# teensyShield1_5.net
KiCad netlist of a schematic drawn in EAGLE
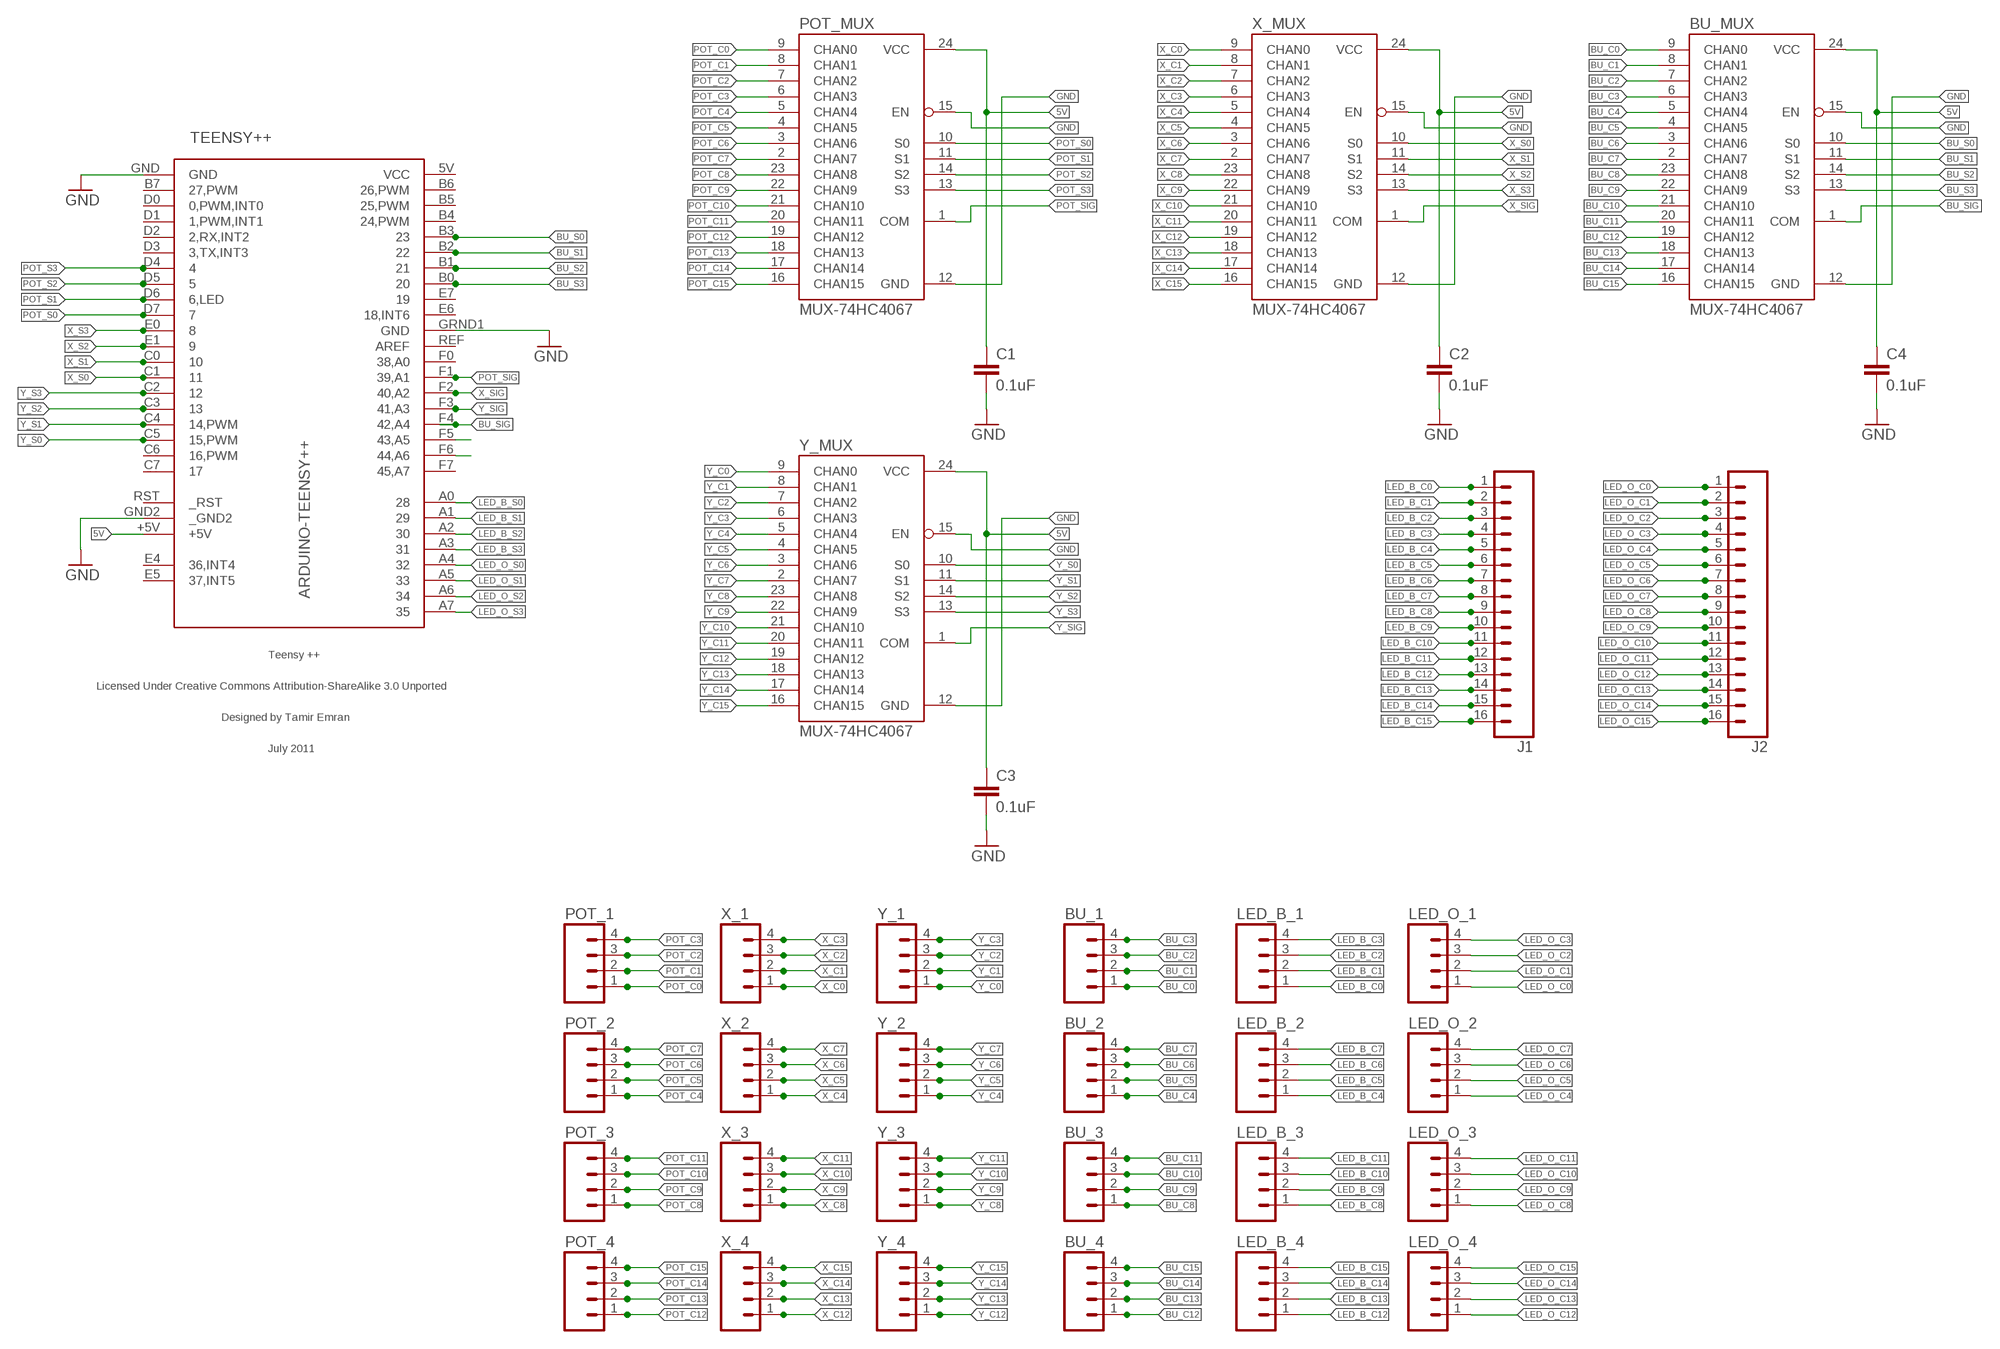
[diagram p0: schematic, sheet 1]

(export (version "E")
  (design (tool "Eeschema 10.0.6"))
  (components
    (comp (ref "BU_1")
      (value "M04NO_SILK_ALL_ROUND")
      (footprint "eagle-import:1X04_NO_SILK_ALL_ROUND")
      (libsource (lib "eagle-import") (part "M04NO_SILK_ALL_ROUND"))
    )
    (comp (ref "BU_2")
      (value "M04NO_SILK_ALL_ROUND")
      (footprint "eagle-import:1X04_NO_SILK_ALL_ROUND")
      (libsource (lib "eagle-import") (part "M04NO_SILK_ALL_ROUND"))
    )
    (comp (ref "BU_3")
      (value "M04NO_SILK_ALL_ROUND")
      (footprint "eagle-import:1X04_NO_SILK_ALL_ROUND")
      (libsource (lib "eagle-import") (part "M04NO_SILK_ALL_ROUND"))
    )
    (comp (ref "BU_4")
      (value "M04NO_SILK_ALL_ROUND")
      (footprint "eagle-import:1X04_NO_SILK_ALL_ROUND")
      (libsource (lib "eagle-import") (part "M04NO_SILK_ALL_ROUND"))
    )
    (comp (ref "BU_MUX")
      (value "MUX-74HC4067")
      (footprint "eagle-import:SSOP24")
      (libsource (lib "eagle-import") (part "MUX-74HC4067SMD"))
    )
    (comp (ref "C1")
      (value "0.1uF")
      (footprint "eagle-import:0603")
      (libsource (lib "eagle-import") (part "CAP0603"))
    )
    (comp (ref "C2")
      (value "0.1uF")
      (footprint "eagle-import:0603")
      (libsource (lib "eagle-import") (part "CAP0603"))
    )
    (comp (ref "C3")
      (value "0.1uF")
      (footprint "eagle-import:0603")
      (libsource (lib "eagle-import") (part "CAP0603"))
    )
    (comp (ref "C4")
      (value "0.1uF")
      (footprint "eagle-import:0603")
      (libsource (lib "eagle-import") (part "CAP0603"))
    )
    (comp (ref "J1")
      (value "M16MACHIINE-PIN_LOCK")
      (footprint "eagle-import:1X16_MACHINE-PIN-HEADER_LOCK.004")
      (libsource (lib "eagle-import") (part "M16MACHIINE-PIN_LOCK"))
    )
    (comp (ref "J2")
      (value "M16MACHIINE-PIN_LOCK")
      (footprint "eagle-import:1X16_MACHINE-PIN-HEADER_LOCK.004")
      (libsource (lib "eagle-import") (part "M16MACHIINE-PIN_LOCK"))
    )
    (comp (ref "LED_B_1")
      (value "M04NO_SILK_ALL_ROUND")
      (footprint "eagle-import:1X04_NO_SILK_ALL_ROUND")
      (libsource (lib "eagle-import") (part "M04NO_SILK_ALL_ROUND"))
    )
    (comp (ref "LED_B_2")
      (value "M04NO_SILK_ALL_ROUND")
      (footprint "eagle-import:1X04_NO_SILK_ALL_ROUND")
      (libsource (lib "eagle-import") (part "M04NO_SILK_ALL_ROUND"))
    )
    (comp (ref "LED_B_3")
      (value "M04NO_SILK_ALL_ROUND")
      (footprint "eagle-import:1X04_NO_SILK_ALL_ROUND")
      (libsource (lib "eagle-import") (part "M04NO_SILK_ALL_ROUND"))
    )
    (comp (ref "LED_B_4")
      (value "M04NO_SILK_ALL_ROUND")
      (footprint "eagle-import:1X04_NO_SILK_ALL_ROUND")
      (libsource (lib "eagle-import") (part "M04NO_SILK_ALL_ROUND"))
    )
    (comp (ref "LED_O_1")
      (value "M04NO_SILK_ALL_ROUND")
      (footprint "eagle-import:1X04_NO_SILK_ALL_ROUND")
      (libsource (lib "eagle-import") (part "M04NO_SILK_ALL_ROUND"))
    )
    (comp (ref "LED_O_2")
      (value "M04NO_SILK_ALL_ROUND")
      (footprint "eagle-import:1X04_NO_SILK_ALL_ROUND")
      (libsource (lib "eagle-import") (part "M04NO_SILK_ALL_ROUND"))
    )
    (comp (ref "LED_O_3")
      (value "M04NO_SILK_ALL_ROUND")
      (footprint "eagle-import:1X04_NO_SILK_ALL_ROUND")
      (libsource (lib "eagle-import") (part "M04NO_SILK_ALL_ROUND"))
    )
    (comp (ref "LED_O_4")
      (value "M04NO_SILK_ALL_ROUND")
      (footprint "eagle-import:1X04_NO_SILK_ALL_ROUND")
      (libsource (lib "eagle-import") (part "M04NO_SILK_ALL_ROUND"))
    )
    (comp (ref "POT_1")
      (value "M04NO_SILK_ALL_ROUND")
      (footprint "eagle-import:1X04_NO_SILK_ALL_ROUND")
      (libsource (lib "eagle-import") (part "M04NO_SILK_ALL_ROUND"))
    )
    (comp (ref "POT_2")
      (value "M04NO_SILK_ALL_ROUND")
      (footprint "eagle-import:1X04_NO_SILK_ALL_ROUND")
      (libsource (lib "eagle-import") (part "M04NO_SILK_ALL_ROUND"))
    )
    (comp (ref "POT_3")
      (value "M04NO_SILK_ALL_ROUND")
      (footprint "eagle-import:1X04_NO_SILK_ALL_ROUND")
      (libsource (lib "eagle-import") (part "M04NO_SILK_ALL_ROUND"))
    )
    (comp (ref "POT_4")
      (value "M04NO_SILK_ALL_ROUND")
      (footprint "eagle-import:1X04_NO_SILK_ALL_ROUND")
      (libsource (lib "eagle-import") (part "M04NO_SILK_ALL_ROUND"))
    )
    (comp (ref "POT_MUX")
      (value "MUX-74HC4067")
      (footprint "eagle-import:SSOP24")
      (libsource (lib "eagle-import") (part "MUX-74HC4067SMD"))
    )
    (comp (ref "TEENSY++")
      (value "ARDUINO-TEENSY++")
      (footprint "eagle-import:TEENSY++")
      (libsource (lib "eagle-import") (part "ARDUINO-TEENSY++"))
    )
    (comp (ref "X_1")
      (value "M04NO_SILK_ALL_ROUND")
      (footprint "eagle-import:1X04_NO_SILK_ALL_ROUND")
      (libsource (lib "eagle-import") (part "M04NO_SILK_ALL_ROUND"))
    )
    (comp (ref "X_2")
      (value "M04NO_SILK_ALL_ROUND")
      (footprint "eagle-import:1X04_NO_SILK_ALL_ROUND")
      (libsource (lib "eagle-import") (part "M04NO_SILK_ALL_ROUND"))
    )
    (comp (ref "X_3")
      (value "M04NO_SILK_ALL_ROUND")
      (footprint "eagle-import:1X04_NO_SILK_ALL_ROUND")
      (libsource (lib "eagle-import") (part "M04NO_SILK_ALL_ROUND"))
    )
    (comp (ref "X_4")
      (value "M04NO_SILK_ALL_ROUND")
      (footprint "eagle-import:1X04_NO_SILK_ALL_ROUND")
      (libsource (lib "eagle-import") (part "M04NO_SILK_ALL_ROUND"))
    )
    (comp (ref "X_MUX")
      (value "MUX-74HC4067")
      (footprint "eagle-import:SSOP24")
      (libsource (lib "eagle-import") (part "MUX-74HC4067SMD"))
    )
    (comp (ref "Y_1")
      (value "M04NO_SILK_ALL_ROUND")
      (footprint "eagle-import:1X04_NO_SILK_ALL_ROUND")
      (libsource (lib "eagle-import") (part "M04NO_SILK_ALL_ROUND"))
    )
    (comp (ref "Y_2")
      (value "M04NO_SILK_ALL_ROUND")
      (footprint "eagle-import:1X04_NO_SILK_ALL_ROUND")
      (libsource (lib "eagle-import") (part "M04NO_SILK_ALL_ROUND"))
    )
    (comp (ref "Y_3")
      (value "M04NO_SILK_ALL_ROUND")
      (footprint "eagle-import:1X04_NO_SILK_ALL_ROUND")
      (libsource (lib "eagle-import") (part "M04NO_SILK_ALL_ROUND"))
    )
    (comp (ref "Y_4")
      (value "M04NO_SILK_ALL_ROUND")
      (footprint "eagle-import:1X04_NO_SILK_ALL_ROUND")
      (libsource (lib "eagle-import") (part "M04NO_SILK_ALL_ROUND"))
    )
    (comp (ref "Y_MUX")
      (value "MUX-74HC4067")
      (footprint "eagle-import:SSOP24")
      (libsource (lib "eagle-import") (part "MUX-74HC4067SMD"))
    )
  )
  (nets
    (net (code "1") (name "/VCC") (class "Default")
      (node (ref "TEENSY++") (pin "5V") (pinfunction "VCC_5V") (pintype "power_in"))
    )
    (net (code "2") (name "5V") (class "Default")
      (node (ref "BU_MUX") (pin "24") (pinfunction "VCC_24") (pintype "bidirectional"))
      (node (ref "C1") (pin "1") (pinfunction "1_1") (pintype "passive"))
      (node (ref "C2") (pin "1") (pinfunction "1_1") (pintype "passive"))
      (node (ref "C3") (pin "1") (pinfunction "1_1") (pintype "passive"))
      (node (ref "C4") (pin "1") (pinfunction "1_1") (pintype "passive"))
      (node (ref "POT_MUX") (pin "24") (pinfunction "VCC_24") (pintype "bidirectional"))
      (node (ref "X_MUX") (pin "24") (pinfunction "VCC_24") (pintype "bidirectional"))
      (node (ref "Y_MUX") (pin "24") (pinfunction "VCC_24") (pintype "bidirectional"))
    )
    (net (code "3") (name "BU_C0") (class "Default")
      (node (ref "BU_1") (pin "1") (pinfunction "1_1") (pintype "passive"))
      (node (ref "BU_MUX") (pin "9") (pinfunction "CHAN0_9") (pintype "bidirectional"))
    )
    (net (code "4") (name "BU_C1") (class "Default")
      (node (ref "BU_1") (pin "2") (pinfunction "2_2") (pintype "passive"))
      (node (ref "BU_MUX") (pin "8") (pinfunction "CHAN1_8") (pintype "bidirectional"))
    )
    (net (code "5") (name "BU_C2") (class "Default")
      (node (ref "BU_1") (pin "3") (pinfunction "3_3") (pintype "passive"))
      (node (ref "BU_MUX") (pin "7") (pinfunction "CHAN2_7") (pintype "bidirectional"))
    )
    (net (code "6") (name "BU_C3") (class "Default")
      (node (ref "BU_1") (pin "4") (pinfunction "4_4") (pintype "passive"))
      (node (ref "BU_MUX") (pin "6") (pinfunction "CHAN3_6") (pintype "bidirectional"))
    )
    (net (code "7") (name "BU_C4") (class "Default")
      (node (ref "BU_2") (pin "1") (pinfunction "1_1") (pintype "passive"))
      (node (ref "BU_MUX") (pin "5") (pinfunction "CHAN4_5") (pintype "bidirectional"))
    )
    (net (code "8") (name "BU_C5") (class "Default")
      (node (ref "BU_2") (pin "2") (pinfunction "2_2") (pintype "passive"))
      (node (ref "BU_MUX") (pin "4") (pinfunction "CHAN5_4") (pintype "bidirectional"))
    )
    (net (code "9") (name "BU_C6") (class "Default")
      (node (ref "BU_2") (pin "3") (pinfunction "3_3") (pintype "passive"))
      (node (ref "BU_MUX") (pin "3") (pinfunction "CHAN6_3") (pintype "bidirectional"))
    )
    (net (code "10") (name "BU_C7") (class "Default")
      (node (ref "BU_2") (pin "4") (pinfunction "4_4") (pintype "passive"))
      (node (ref "BU_MUX") (pin "2") (pinfunction "CHAN7_2") (pintype "bidirectional"))
    )
    (net (code "11") (name "BU_C8") (class "Default")
      (node (ref "BU_3") (pin "1") (pinfunction "1_1") (pintype "passive"))
      (node (ref "BU_MUX") (pin "23") (pinfunction "CHAN8_23") (pintype "bidirectional"))
    )
    (net (code "12") (name "BU_C9") (class "Default")
      (node (ref "BU_3") (pin "2") (pinfunction "2_2") (pintype "passive"))
      (node (ref "BU_MUX") (pin "22") (pinfunction "CHAN9_22") (pintype "bidirectional"))
    )
    (net (code "13") (name "BU_C10") (class "Default")
      (node (ref "BU_3") (pin "3") (pinfunction "3_3") (pintype "passive"))
      (node (ref "BU_MUX") (pin "21") (pinfunction "CHAN10_21") (pintype "bidirectional"))
    )
    (net (code "14") (name "BU_C11") (class "Default")
      (node (ref "BU_3") (pin "4") (pinfunction "4_4") (pintype "passive"))
      (node (ref "BU_MUX") (pin "20") (pinfunction "CHAN11_20") (pintype "bidirectional"))
    )
    (net (code "15") (name "BU_C12") (class "Default")
      (node (ref "BU_4") (pin "1") (pinfunction "1_1") (pintype "passive"))
      (node (ref "BU_MUX") (pin "19") (pinfunction "CHAN12_19") (pintype "bidirectional"))
    )
    (net (code "16") (name "BU_C13") (class "Default")
      (node (ref "BU_4") (pin "2") (pinfunction "2_2") (pintype "passive"))
      (node (ref "BU_MUX") (pin "18") (pinfunction "CHAN13_18") (pintype "bidirectional"))
    )
    (net (code "17") (name "BU_C14") (class "Default")
      (node (ref "BU_4") (pin "3") (pinfunction "3_3") (pintype "passive"))
      (node (ref "BU_MUX") (pin "17") (pinfunction "CHAN14_17") (pintype "bidirectional"))
    )
    (net (code "18") (name "BU_C15") (class "Default")
      (node (ref "BU_4") (pin "4") (pinfunction "4_4") (pintype "passive"))
      (node (ref "BU_MUX") (pin "16") (pinfunction "CHAN15_16") (pintype "bidirectional"))
    )
    (net (code "19") (name "BU_S0") (class "Default")
      (node (ref "BU_MUX") (pin "10") (pinfunction "S0_10") (pintype "input"))
      (node (ref "TEENSY++") (pin "B3") (pinfunction "23_B3") (pintype "bidirectional"))
    )
    (net (code "20") (name "BU_S1") (class "Default")
      (node (ref "BU_MUX") (pin "11") (pinfunction "S1_11") (pintype "input"))
      (node (ref "TEENSY++") (pin "B2") (pinfunction "22_B2") (pintype "bidirectional"))
    )
    (net (code "21") (name "BU_S2") (class "Default")
      (node (ref "BU_MUX") (pin "14") (pinfunction "S2_14") (pintype "input"))
      (node (ref "TEENSY++") (pin "B1") (pinfunction "21_B1") (pintype "bidirectional"))
    )
    (net (code "22") (name "BU_S3") (class "Default")
      (node (ref "BU_MUX") (pin "13") (pinfunction "S3_13") (pintype "input"))
      (node (ref "TEENSY++") (pin "B0") (pinfunction "20_B0") (pintype "bidirectional"))
    )
    (net (code "23") (name "BU_SIG") (class "Default")
      (node (ref "BU_MUX") (pin "1") (pinfunction "COM_1") (pintype "bidirectional"))
      (node (ref "TEENSY++") (pin "F4") (pinfunction "42,A4_F4") (pintype "bidirectional"))
    )
    (net (code "24") (name "GND") (class "Default")
      (node (ref "BU_MUX") (pin "12") (pinfunction "GND_12") (pintype "bidirectional"))
      (node (ref "BU_MUX") (pin "15") (pinfunction "EN_15") (pintype "input"))
      (node (ref "C1") (pin "2") (pinfunction "2_2") (pintype "passive"))
      (node (ref "C2") (pin "2") (pinfunction "2_2") (pintype "passive"))
      (node (ref "C3") (pin "2") (pinfunction "2_2") (pintype "passive"))
      (node (ref "C4") (pin "2") (pinfunction "2_2") (pintype "passive"))
      (node (ref "POT_MUX") (pin "12") (pinfunction "GND_12") (pintype "bidirectional"))
      (node (ref "POT_MUX") (pin "15") (pinfunction "EN_15") (pintype "input"))
      (node (ref "TEENSY++") (pin "GND") (pinfunction "GND_GND") (pintype "power_in"))
      (node (ref "TEENSY++") (pin "GND2") (pinfunction "_GND2_GND2") (pintype "power_in"))
      (node (ref "TEENSY++") (pin "GRND1") (pinfunction "GND_GRND1") (pintype "power_in"))
      (node (ref "X_MUX") (pin "12") (pinfunction "GND_12") (pintype "bidirectional"))
      (node (ref "X_MUX") (pin "15") (pinfunction "EN_15") (pintype "input"))
      (node (ref "Y_MUX") (pin "12") (pinfunction "GND_12") (pintype "bidirectional"))
      (node (ref "Y_MUX") (pin "15") (pinfunction "EN_15") (pintype "input"))
    )
    (net (code "25") (name "LED_B_C0") (class "Default")
      (node (ref "J1") (pin "1") (pinfunction "1_1") (pintype "passive"))
      (node (ref "LED_B_1") (pin "1") (pinfunction "1_1") (pintype "passive"))
    )
    (net (code "26") (name "LED_B_C1") (class "Default")
      (node (ref "J1") (pin "2") (pinfunction "2_2") (pintype "passive"))
      (node (ref "LED_B_1") (pin "2") (pinfunction "2_2") (pintype "passive"))
    )
    (net (code "27") (name "LED_B_C2") (class "Default")
      (node (ref "J1") (pin "3") (pinfunction "3_3") (pintype "passive"))
      (node (ref "LED_B_1") (pin "3") (pinfunction "3_3") (pintype "passive"))
    )
    (net (code "28") (name "LED_B_C3") (class "Default")
      (node (ref "J1") (pin "4") (pinfunction "4_4") (pintype "passive"))
      (node (ref "LED_B_1") (pin "4") (pinfunction "4_4") (pintype "passive"))
    )
    (net (code "29") (name "LED_B_C4") (class "Default")
      (node (ref "J1") (pin "5") (pinfunction "5_5") (pintype "passive"))
      (node (ref "LED_B_2") (pin "1") (pinfunction "1_1") (pintype "passive"))
    )
    (net (code "30") (name "LED_B_C5") (class "Default")
      (node (ref "J1") (pin "6") (pinfunction "6_6") (pintype "passive"))
      (node (ref "LED_B_2") (pin "2") (pinfunction "2_2") (pintype "passive"))
    )
    (net (code "31") (name "LED_B_C6") (class "Default")
      (node (ref "J1") (pin "7") (pinfunction "7_7") (pintype "passive"))
      (node (ref "LED_B_2") (pin "3") (pinfunction "3_3") (pintype "passive"))
    )
    (net (code "32") (name "LED_B_C7") (class "Default")
      (node (ref "J1") (pin "8") (pinfunction "8_8") (pintype "passive"))
      (node (ref "LED_B_2") (pin "4") (pinfunction "4_4") (pintype "passive"))
    )
    (net (code "33") (name "LED_B_C8") (class "Default")
      (node (ref "J1") (pin "9") (pinfunction "9_9") (pintype "passive"))
      (node (ref "LED_B_3") (pin "1") (pinfunction "1_1") (pintype "passive"))
    )
    (net (code "34") (name "LED_B_C9") (class "Default")
      (node (ref "J1") (pin "10") (pinfunction "10_10") (pintype "passive"))
      (node (ref "LED_B_3") (pin "2") (pinfunction "2_2") (pintype "passive"))
    )
    (net (code "35") (name "LED_B_C10") (class "Default")
      (node (ref "J1") (pin "11") (pinfunction "11_11") (pintype "passive"))
      (node (ref "LED_B_3") (pin "3") (pinfunction "3_3") (pintype "passive"))
    )
    (net (code "36") (name "LED_B_C11") (class "Default")
      (node (ref "J1") (pin "12") (pinfunction "12_12") (pintype "passive"))
      (node (ref "LED_B_3") (pin "4") (pinfunction "4_4") (pintype "passive"))
    )
    (net (code "37") (name "LED_B_C12") (class "Default")
      (node (ref "J1") (pin "13") (pinfunction "13_13") (pintype "passive"))
      (node (ref "LED_B_4") (pin "1") (pinfunction "1_1") (pintype "passive"))
    )
    (net (code "38") (name "LED_B_C13") (class "Default")
      (node (ref "J1") (pin "14") (pinfunction "14_14") (pintype "passive"))
      (node (ref "LED_B_4") (pin "2") (pinfunction "2_2") (pintype "passive"))
    )
    (net (code "39") (name "LED_B_C14") (class "Default")
      (node (ref "J1") (pin "15") (pinfunction "15_15") (pintype "passive"))
      (node (ref "LED_B_4") (pin "3") (pinfunction "3_3") (pintype "passive"))
    )
    (net (code "40") (name "LED_B_C15") (class "Default")
      (node (ref "J1") (pin "16") (pinfunction "16_16") (pintype "passive"))
      (node (ref "LED_B_4") (pin "4") (pinfunction "4_4") (pintype "passive"))
    )
    (net (code "41") (name "LED_B_S0") (class "Default")
      (node (ref "TEENSY++") (pin "A0") (pinfunction "28_A0") (pintype "bidirectional"))
    )
    (net (code "42") (name "LED_B_S1") (class "Default")
      (node (ref "TEENSY++") (pin "A1") (pinfunction "29_A1") (pintype "bidirectional"))
    )
    (net (code "43") (name "LED_B_S2") (class "Default")
      (node (ref "TEENSY++") (pin "A2") (pinfunction "30_A2") (pintype "bidirectional"))
    )
    (net (code "44") (name "LED_B_S3") (class "Default")
      (node (ref "TEENSY++") (pin "A3") (pinfunction "31_A3") (pintype "bidirectional"))
    )
    (net (code "45") (name "LED_O_C0") (class "Default")
      (node (ref "J2") (pin "1") (pinfunction "1_1") (pintype "passive"))
      (node (ref "LED_O_1") (pin "1") (pinfunction "1_1") (pintype "passive"))
    )
    (net (code "46") (name "LED_O_C1") (class "Default")
      (node (ref "J2") (pin "2") (pinfunction "2_2") (pintype "passive"))
      (node (ref "LED_O_1") (pin "2") (pinfunction "2_2") (pintype "passive"))
    )
    (net (code "47") (name "LED_O_C2") (class "Default")
      (node (ref "J2") (pin "3") (pinfunction "3_3") (pintype "passive"))
      (node (ref "LED_O_1") (pin "3") (pinfunction "3_3") (pintype "passive"))
    )
    (net (code "48") (name "LED_O_C3") (class "Default")
      (node (ref "J2") (pin "4") (pinfunction "4_4") (pintype "passive"))
      (node (ref "LED_O_1") (pin "4") (pinfunction "4_4") (pintype "passive"))
    )
    (net (code "49") (name "LED_O_C4") (class "Default")
      (node (ref "J2") (pin "5") (pinfunction "5_5") (pintype "passive"))
      (node (ref "LED_O_2") (pin "1") (pinfunction "1_1") (pintype "passive"))
    )
    (net (code "50") (name "LED_O_C5") (class "Default")
      (node (ref "J2") (pin "6") (pinfunction "6_6") (pintype "passive"))
      (node (ref "LED_O_2") (pin "2") (pinfunction "2_2") (pintype "passive"))
    )
    (net (code "51") (name "LED_O_C6") (class "Default")
      (node (ref "J2") (pin "7") (pinfunction "7_7") (pintype "passive"))
      (node (ref "LED_O_2") (pin "3") (pinfunction "3_3") (pintype "passive"))
    )
    (net (code "52") (name "LED_O_C7") (class "Default")
      (node (ref "J2") (pin "8") (pinfunction "8_8") (pintype "passive"))
      (node (ref "LED_O_2") (pin "4") (pinfunction "4_4") (pintype "passive"))
    )
    (net (code "53") (name "LED_O_C8") (class "Default")
      (node (ref "J2") (pin "9") (pinfunction "9_9") (pintype "passive"))
      (node (ref "LED_O_3") (pin "1") (pinfunction "1_1") (pintype "passive"))
    )
    (net (code "54") (name "LED_O_C9") (class "Default")
      (node (ref "J2") (pin "10") (pinfunction "10_10") (pintype "passive"))
      (node (ref "LED_O_3") (pin "2") (pinfunction "2_2") (pintype "passive"))
    )
    (net (code "55") (name "LED_O_C10") (class "Default")
      (node (ref "J2") (pin "11") (pinfunction "11_11") (pintype "passive"))
      (node (ref "LED_O_3") (pin "3") (pinfunction "3_3") (pintype "passive"))
    )
    (net (code "56") (name "LED_O_C11") (class "Default")
      (node (ref "J2") (pin "12") (pinfunction "12_12") (pintype "passive"))
      (node (ref "LED_O_3") (pin "4") (pinfunction "4_4") (pintype "passive"))
    )
    (net (code "57") (name "LED_O_C12") (class "Default")
      (node (ref "J2") (pin "13") (pinfunction "13_13") (pintype "passive"))
      (node (ref "LED_O_4") (pin "1") (pinfunction "1_1") (pintype "passive"))
    )
    (net (code "58") (name "LED_O_C13") (class "Default")
      (node (ref "J2") (pin "14") (pinfunction "14_14") (pintype "passive"))
      (node (ref "LED_O_4") (pin "2") (pinfunction "2_2") (pintype "passive"))
    )
    (net (code "59") (name "LED_O_C14") (class "Default")
      (node (ref "J2") (pin "15") (pinfunction "15_15") (pintype "passive"))
      (node (ref "LED_O_4") (pin "3") (pinfunction "3_3") (pintype "passive"))
    )
    (net (code "60") (name "LED_O_C15") (class "Default")
      (node (ref "J2") (pin "16") (pinfunction "16_16") (pintype "passive"))
      (node (ref "LED_O_4") (pin "4") (pinfunction "4_4") (pintype "passive"))
    )
    (net (code "61") (name "LED_O_S0") (class "Default")
      (node (ref "TEENSY++") (pin "A4") (pinfunction "32_A4") (pintype "bidirectional"))
    )
    (net (code "62") (name "LED_O_S1") (class "Default")
      (node (ref "TEENSY++") (pin "A5") (pinfunction "33_A5") (pintype "bidirectional"))
    )
    (net (code "63") (name "LED_O_S2") (class "Default")
      (node (ref "TEENSY++") (pin "A6") (pinfunction "34_A6") (pintype "bidirectional"))
    )
    (net (code "64") (name "LED_O_S3") (class "Default")
      (node (ref "TEENSY++") (pin "A7") (pinfunction "35_A7") (pintype "bidirectional"))
    )
    (net (code "65") (name "POT_C0") (class "Default")
      (node (ref "POT_1") (pin "1") (pinfunction "1_1") (pintype "passive"))
      (node (ref "POT_MUX") (pin "9") (pinfunction "CHAN0_9") (pintype "bidirectional"))
    )
    (net (code "66") (name "POT_C1") (class "Default")
      (node (ref "POT_1") (pin "2") (pinfunction "2_2") (pintype "passive"))
      (node (ref "POT_MUX") (pin "8") (pinfunction "CHAN1_8") (pintype "bidirectional"))
    )
    (net (code "67") (name "POT_C2") (class "Default")
      (node (ref "POT_1") (pin "3") (pinfunction "3_3") (pintype "passive"))
      (node (ref "POT_MUX") (pin "7") (pinfunction "CHAN2_7") (pintype "bidirectional"))
    )
    (net (code "68") (name "POT_C3") (class "Default")
      (node (ref "POT_1") (pin "4") (pinfunction "4_4") (pintype "passive"))
      (node (ref "POT_MUX") (pin "6") (pinfunction "CHAN3_6") (pintype "bidirectional"))
    )
    (net (code "69") (name "POT_C4") (class "Default")
      (node (ref "POT_2") (pin "1") (pinfunction "1_1") (pintype "passive"))
      (node (ref "POT_MUX") (pin "5") (pinfunction "CHAN4_5") (pintype "bidirectional"))
    )
    (net (code "70") (name "POT_C5") (class "Default")
      (node (ref "POT_2") (pin "2") (pinfunction "2_2") (pintype "passive"))
      (node (ref "POT_MUX") (pin "4") (pinfunction "CHAN5_4") (pintype "bidirectional"))
    )
    (net (code "71") (name "POT_C6") (class "Default")
      (node (ref "POT_2") (pin "3") (pinfunction "3_3") (pintype "passive"))
      (node (ref "POT_MUX") (pin "3") (pinfunction "CHAN6_3") (pintype "bidirectional"))
    )
    (net (code "72") (name "POT_C7") (class "Default")
      (node (ref "POT_2") (pin "4") (pinfunction "4_4") (pintype "passive"))
      (node (ref "POT_MUX") (pin "2") (pinfunction "CHAN7_2") (pintype "bidirectional"))
    )
    (net (code "73") (name "POT_C8") (class "Default")
      (node (ref "POT_3") (pin "1") (pinfunction "1_1") (pintype "passive"))
      (node (ref "POT_MUX") (pin "23") (pinfunction "CHAN8_23") (pintype "bidirectional"))
    )
    (net (code "74") (name "POT_C9") (class "Default")
      (node (ref "POT_3") (pin "2") (pinfunction "2_2") (pintype "passive"))
      (node (ref "POT_MUX") (pin "22") (pinfunction "CHAN9_22") (pintype "bidirectional"))
    )
    (net (code "75") (name "POT_C10") (class "Default")
      (node (ref "POT_3") (pin "3") (pinfunction "3_3") (pintype "passive"))
      (node (ref "POT_MUX") (pin "21") (pinfunction "CHAN10_21") (pintype "bidirectional"))
    )
    (net (code "76") (name "POT_C11") (class "Default")
      (node (ref "POT_3") (pin "4") (pinfunction "4_4") (pintype "passive"))
      (node (ref "POT_MUX") (pin "20") (pinfunction "CHAN11_20") (pintype "bidirectional"))
    )
    (net (code "77") (name "POT_C12") (class "Default")
      (node (ref "POT_4") (pin "1") (pinfunction "1_1") (pintype "passive"))
      (node (ref "POT_MUX") (pin "19") (pinfunction "CHAN12_19") (pintype "bidirectional"))
    )
    (net (code "78") (name "POT_C13") (class "Default")
      (node (ref "POT_4") (pin "2") (pinfunction "2_2") (pintype "passive"))
      (node (ref "POT_MUX") (pin "18") (pinfunction "CHAN13_18") (pintype "bidirectional"))
    )
    (net (code "79") (name "POT_C14") (class "Default")
      (node (ref "POT_4") (pin "3") (pinfunction "3_3") (pintype "passive"))
      (node (ref "POT_MUX") (pin "17") (pinfunction "CHAN14_17") (pintype "bidirectional"))
    )
    (net (code "80") (name "POT_C15") (class "Default")
      (node (ref "POT_4") (pin "4") (pinfunction "4_4") (pintype "passive"))
      (node (ref "POT_MUX") (pin "16") (pinfunction "CHAN15_16") (pintype "bidirectional"))
    )
    (net (code "81") (name "POT_S0") (class "Default")
      (node (ref "POT_MUX") (pin "10") (pinfunction "S0_10") (pintype "input"))
      (node (ref "TEENSY++") (pin "D7") (pinfunction "7_D7") (pintype "bidirectional"))
    )
    (net (code "82") (name "POT_S1") (class "Default")
      (node (ref "POT_MUX") (pin "11") (pinfunction "S1_11") (pintype "input"))
      (node (ref "TEENSY++") (pin "D6") (pinfunction "6,LED_D6") (pintype "bidirectional"))
    )
    (net (code "83") (name "POT_S2") (class "Default")
      (node (ref "POT_MUX") (pin "14") (pinfunction "S2_14") (pintype "input"))
      (node (ref "TEENSY++") (pin "D5") (pinfunction "5_D5") (pintype "bidirectional"))
    )
    (net (code "84") (name "POT_S3") (class "Default")
      (node (ref "POT_MUX") (pin "13") (pinfunction "S3_13") (pintype "input"))
      (node (ref "TEENSY++") (pin "D4") (pinfunction "4_D4") (pintype "bidirectional"))
    )
    (net (code "85") (name "POT_SIG") (class "Default")
      (node (ref "POT_MUX") (pin "1") (pinfunction "COM_1") (pintype "bidirectional"))
    )
    (net (code "86") (name "X_C0") (class "Default")
      (node (ref "X_1") (pin "1") (pinfunction "1_1") (pintype "passive"))
      (node (ref "X_MUX") (pin "9") (pinfunction "CHAN0_9") (pintype "bidirectional"))
    )
    (net (code "87") (name "X_C1") (class "Default")
      (node (ref "X_1") (pin "2") (pinfunction "2_2") (pintype "passive"))
      (node (ref "X_MUX") (pin "8") (pinfunction "CHAN1_8") (pintype "bidirectional"))
    )
    (net (code "88") (name "X_C2") (class "Default")
      (node (ref "X_1") (pin "3") (pinfunction "3_3") (pintype "passive"))
      (node (ref "X_MUX") (pin "7") (pinfunction "CHAN2_7") (pintype "bidirectional"))
    )
    (net (code "89") (name "X_C3") (class "Default")
      (node (ref "X_1") (pin "4") (pinfunction "4_4") (pintype "passive"))
      (node (ref "X_MUX") (pin "6") (pinfunction "CHAN3_6") (pintype "bidirectional"))
    )
    (net (code "90") (name "X_C4") (class "Default")
      (node (ref "X_2") (pin "1") (pinfunction "1_1") (pintype "passive"))
      (node (ref "X_MUX") (pin "5") (pinfunction "CHAN4_5") (pintype "bidirectional"))
    )
    (net (code "91") (name "X_C5") (class "Default")
      (node (ref "X_2") (pin "2") (pinfunction "2_2") (pintype "passive"))
      (node (ref "X_MUX") (pin "4") (pinfunction "CHAN5_4") (pintype "bidirectional"))
    )
    (net (code "92") (name "X_C6") (class "Default")
      (node (ref "X_2") (pin "3") (pinfunction "3_3") (pintype "passive"))
      (node (ref "X_MUX") (pin "3") (pinfunction "CHAN6_3") (pintype "bidirectional"))
    )
    (net (code "93") (name "X_C7") (class "Default")
      (node (ref "X_2") (pin "4") (pinfunction "4_4") (pintype "passive"))
      (node (ref "X_MUX") (pin "2") (pinfunction "CHAN7_2") (pintype "bidirectional"))
    )
    (net (code "94") (name "X_C8") (class "Default")
      (node (ref "X_3") (pin "1") (pinfunction "1_1") (pintype "passive"))
      (node (ref "X_MUX") (pin "23") (pinfunction "CHAN8_23") (pintype "bidirectional"))
    )
    (net (code "95") (name "X_C9") (class "Default")
      (node (ref "X_3") (pin "2") (pinfunction "2_2") (pintype "passive"))
      (node (ref "X_MUX") (pin "22") (pinfunction "CHAN9_22") (pintype "bidirectional"))
    )
    (net (code "96") (name "X_C10") (class "Default")
      (node (ref "X_3") (pin "3") (pinfunction "3_3") (pintype "passive"))
      (node (ref "X_MUX") (pin "21") (pinfunction "CHAN10_21") (pintype "bidirectional"))
    )
    (net (code "97") (name "X_C11") (class "Default")
      (node (ref "X_3") (pin "4") (pinfunction "4_4") (pintype "passive"))
      (node (ref "X_MUX") (pin "20") (pinfunction "CHAN11_20") (pintype "bidirectional"))
    )
    (net (code "98") (name "X_C12") (class "Default")
      (node (ref "X_4") (pin "1") (pinfunction "1_1") (pintype "passive"))
      (node (ref "X_MUX") (pin "19") (pinfunction "CHAN12_19") (pintype "bidirectional"))
    )
    (net (code "99") (name "X_C13") (class "Default")
      (node (ref "X_4") (pin "2") (pinfunction "2_2") (pintype "passive"))
      (node (ref "X_MUX") (pin "18") (pinfunction "CHAN13_18") (pintype "bidirectional"))
    )
    (net (code "100") (name "X_C14") (class "Default")
      (node (ref "X_4") (pin "3") (pinfunction "3_3") (pintype "passive"))
      (node (ref "X_MUX") (pin "17") (pinfunction "CHAN14_17") (pintype "bidirectional"))
    )
    (net (code "101") (name "X_C15") (class "Default")
      (node (ref "X_4") (pin "4") (pinfunction "4_4") (pintype "passive"))
      (node (ref "X_MUX") (pin "16") (pinfunction "CHAN15_16") (pintype "bidirectional"))
    )
    (net (code "102") (name "X_S0") (class "Default")
      (node (ref "TEENSY++") (pin "C1") (pinfunction "11_C1") (pintype "bidirectional"))
      (node (ref "X_MUX") (pin "10") (pinfunction "S0_10") (pintype "input"))
    )
    (net (code "103") (name "X_S1") (class "Default")
      (node (ref "TEENSY++") (pin "C0") (pinfunction "10_C0") (pintype "bidirectional"))
      (node (ref "X_MUX") (pin "11") (pinfunction "S1_11") (pintype "input"))
    )
    (net (code "104") (name "X_S2") (class "Default")
      (node (ref "TEENSY++") (pin "E1") (pinfunction "9_E1") (pintype "bidirectional"))
      (node (ref "X_MUX") (pin "14") (pinfunction "S2_14") (pintype "input"))
    )
    (net (code "105") (name "X_S3") (class "Default")
      (node (ref "TEENSY++") (pin "E0") (pinfunction "8_E0") (pintype "bidirectional"))
      (node (ref "X_MUX") (pin "13") (pinfunction "S3_13") (pintype "input"))
    )
    (net (code "106") (name "X_SIG") (class "Default")
      (node (ref "X_MUX") (pin "1") (pinfunction "COM_1") (pintype "bidirectional"))
    )
    (net (code "107") (name "Y_C0") (class "Default")
      (node (ref "Y_1") (pin "1") (pinfunction "1_1") (pintype "passive"))
      (node (ref "Y_MUX") (pin "9") (pinfunction "CHAN0_9") (pintype "bidirectional"))
    )
    (net (code "108") (name "Y_C1") (class "Default")
      (node (ref "Y_1") (pin "2") (pinfunction "2_2") (pintype "passive"))
      (node (ref "Y_MUX") (pin "8") (pinfunction "CHAN1_8") (pintype "bidirectional"))
    )
    (net (code "109") (name "Y_C2") (class "Default")
      (node (ref "Y_1") (pin "3") (pinfunction "3_3") (pintype "passive"))
      (node (ref "Y_MUX") (pin "7") (pinfunction "CHAN2_7") (pintype "bidirectional"))
    )
    (net (code "110") (name "Y_C3") (class "Default")
      (node (ref "Y_1") (pin "4") (pinfunction "4_4") (pintype "passive"))
      (node (ref "Y_MUX") (pin "6") (pinfunction "CHAN3_6") (pintype "bidirectional"))
    )
    (net (code "111") (name "Y_C4") (class "Default")
      (node (ref "Y_2") (pin "1") (pinfunction "1_1") (pintype "passive"))
      (node (ref "Y_MUX") (pin "5") (pinfunction "CHAN4_5") (pintype "bidirectional"))
    )
    (net (code "112") (name "Y_C5") (class "Default")
      (node (ref "Y_2") (pin "2") (pinfunction "2_2") (pintype "passive"))
      (node (ref "Y_MUX") (pin "4") (pinfunction "CHAN5_4") (pintype "bidirectional"))
    )
    (net (code "113") (name "Y_C6") (class "Default")
      (node (ref "Y_2") (pin "3") (pinfunction "3_3") (pintype "passive"))
      (node (ref "Y_MUX") (pin "3") (pinfunction "CHAN6_3") (pintype "bidirectional"))
    )
    (net (code "114") (name "Y_C7") (class "Default")
      (node (ref "Y_2") (pin "4") (pinfunction "4_4") (pintype "passive"))
      (node (ref "Y_MUX") (pin "2") (pinfunction "CHAN7_2") (pintype "bidirectional"))
    )
    (net (code "115") (name "Y_C8") (class "Default")
      (node (ref "Y_3") (pin "1") (pinfunction "1_1") (pintype "passive"))
      (node (ref "Y_MUX") (pin "23") (pinfunction "CHAN8_23") (pintype "bidirectional"))
    )
    (net (code "116") (name "Y_C9") (class "Default")
      (node (ref "Y_3") (pin "2") (pinfunction "2_2") (pintype "passive"))
      (node (ref "Y_MUX") (pin "22") (pinfunction "CHAN9_22") (pintype "bidirectional"))
    )
    (net (code "117") (name "Y_C10") (class "Default")
      (node (ref "Y_3") (pin "3") (pinfunction "3_3") (pintype "passive"))
      (node (ref "Y_MUX") (pin "21") (pinfunction "CHAN10_21") (pintype "bidirectional"))
    )
    (net (code "118") (name "Y_C11") (class "Default")
      (node (ref "Y_3") (pin "4") (pinfunction "4_4") (pintype "passive"))
      (node (ref "Y_MUX") (pin "20") (pinfunction "CHAN11_20") (pintype "bidirectional"))
    )
    (net (code "119") (name "Y_C12") (class "Default")
      (node (ref "Y_4") (pin "1") (pinfunction "1_1") (pintype "passive"))
      (node (ref "Y_MUX") (pin "19") (pinfunction "CHAN12_19") (pintype "bidirectional"))
    )
    (net (code "120") (name "Y_C13") (class "Default")
      (node (ref "Y_4") (pin "2") (pinfunction "2_2") (pintype "passive"))
      (node (ref "Y_MUX") (pin "18") (pinfunction "CHAN13_18") (pintype "bidirectional"))
    )
    (net (code "121") (name "Y_C14") (class "Default")
      (node (ref "Y_4") (pin "3") (pinfunction "3_3") (pintype "passive"))
      (node (ref "Y_MUX") (pin "17") (pinfunction "CHAN14_17") (pintype "bidirectional"))
    )
    (net (code "122") (name "Y_C15") (class "Default")
      (node (ref "Y_4") (pin "4") (pinfunction "4_4") (pintype "passive"))
      (node (ref "Y_MUX") (pin "16") (pinfunction "CHAN15_16") (pintype "bidirectional"))
    )
    (net (code "123") (name "Y_S0") (class "Default")
      (node (ref "TEENSY++") (pin "C5") (pinfunction "15,PWM_C5") (pintype "bidirectional"))
      (node (ref "Y_MUX") (pin "10") (pinfunction "S0_10") (pintype "input"))
    )
    (net (code "124") (name "Y_S1") (class "Default")
      (node (ref "TEENSY++") (pin "C4") (pinfunction "14,PWM_C4") (pintype "bidirectional"))
      (node (ref "Y_MUX") (pin "11") (pinfunction "S1_11") (pintype "input"))
    )
    (net (code "125") (name "Y_S2") (class "Default")
      (node (ref "TEENSY++") (pin "C3") (pinfunction "13_C3") (pintype "bidirectional"))
      (node (ref "Y_MUX") (pin "14") (pinfunction "S2_14") (pintype "input"))
    )
    (net (code "126") (name "Y_S3") (class "Default")
      (node (ref "TEENSY++") (pin "C2") (pinfunction "12_C2") (pintype "bidirectional"))
      (node (ref "Y_MUX") (pin "13") (pinfunction "S3_13") (pintype "input"))
    )
    (net (code "127") (name "Y_SIG") (class "Default")
      (node (ref "TEENSY++") (pin "F3") (pinfunction "41,A3_F3") (pintype "bidirectional"))
      (node (ref "Y_MUX") (pin "1") (pinfunction "COM_1") (pintype "bidirectional"))
    )
    (net (code "128") (name "unconnected-(TEENSY++-0,PWM,INT0-PadD0)") (class "Default")
      (node (ref "TEENSY++") (pin "D0") (pinfunction "0,PWM,INT0_D0") (pintype "bidirectional"))
    )
    (net (code "129") (name "unconnected-(TEENSY++-1,PWM,INT1-PadD1)") (class "Default")
      (node (ref "TEENSY++") (pin "D1") (pinfunction "1,PWM,INT1_D1") (pintype "bidirectional"))
    )
    (net (code "130") (name "unconnected-(TEENSY++-2,RX,INT2-PadD2)") (class "Default")
      (node (ref "TEENSY++") (pin "D2") (pinfunction "2,RX,INT2_D2") (pintype "bidirectional"))
    )
    (net (code "131") (name "unconnected-(TEENSY++-3,TX,INT3-PadD3)") (class "Default")
      (node (ref "TEENSY++") (pin "D3") (pinfunction "3,TX,INT3_D3") (pintype "bidirectional"))
    )
    (net (code "132") (name "unconnected-(TEENSY++-16,PWM-PadC6)") (class "Default")
      (node (ref "TEENSY++") (pin "C6") (pinfunction "16,PWM_C6") (pintype "bidirectional"))
    )
    (net (code "133") (name "unconnected-(TEENSY++-17-PadC7)") (class "Default")
      (node (ref "TEENSY++") (pin "C7") (pinfunction "17_C7") (pintype "bidirectional"))
    )
    (net (code "134") (name "unconnected-(TEENSY++-18,INT6-PadE6)") (class "Default")
      (node (ref "TEENSY++") (pin "E6") (pinfunction "18,INT6_E6") (pintype "bidirectional"))
    )
    (net (code "135") (name "unconnected-(TEENSY++-19-PadE7)") (class "Default")
      (node (ref "TEENSY++") (pin "E7") (pinfunction "19_E7") (pintype "bidirectional"))
    )
    (net (code "136") (name "unconnected-(TEENSY++-24,PWM-PadB4)") (class "Default")
      (node (ref "TEENSY++") (pin "B4") (pinfunction "24,PWM_B4") (pintype "bidirectional"))
    )
    (net (code "137") (name "unconnected-(TEENSY++-25,PWM-PadB5)") (class "Default")
      (node (ref "TEENSY++") (pin "B5") (pinfunction "25,PWM_B5") (pintype "bidirectional"))
    )
    (net (code "138") (name "unconnected-(TEENSY++-26,PWM-PadB6)") (class "Default")
      (node (ref "TEENSY++") (pin "B6") (pinfunction "26,PWM_B6") (pintype "bidirectional"))
    )
    (net (code "139") (name "unconnected-(TEENSY++-27,PWM-PadB7)") (class "Default")
      (node (ref "TEENSY++") (pin "B7") (pinfunction "27,PWM_B7") (pintype "bidirectional"))
    )
    (net (code "140") (name "unconnected-(TEENSY++-36,INT4-PadE4)") (class "Default")
      (node (ref "TEENSY++") (pin "E4") (pinfunction "36,INT4_E4") (pintype "bidirectional"))
    )
    (net (code "141") (name "unconnected-(TEENSY++-37,INT5-PadE5)") (class "Default")
      (node (ref "TEENSY++") (pin "E5") (pinfunction "37,INT5_E5") (pintype "bidirectional"))
    )
    (net (code "142") (name "unconnected-(TEENSY++-38,A0-PadF0)") (class "Default")
      (node (ref "TEENSY++") (pin "F0") (pinfunction "38,A0_F0") (pintype "bidirectional"))
    )
    (net (code "143") (name "unconnected-(TEENSY++-39,A1-PadF1)") (class "Default")
      (node (ref "TEENSY++") (pin "F1") (pinfunction "39,A1_F1") (pintype "bidirectional"))
    )
    (net (code "144") (name "unconnected-(TEENSY++-40,A2-PadF2)") (class "Default")
      (node (ref "TEENSY++") (pin "F2") (pinfunction "40,A2_F2") (pintype "bidirectional"))
    )
    (net (code "145") (name "unconnected-(TEENSY++-43,A5-PadF5)") (class "Default")
      (node (ref "TEENSY++") (pin "F5") (pinfunction "43,A5_F5") (pintype "bidirectional"))
    )
    (net (code "146") (name "unconnected-(TEENSY++-44,A6-PadF6)") (class "Default")
      (node (ref "TEENSY++") (pin "F6") (pinfunction "44,A6_F6") (pintype "bidirectional"))
    )
    (net (code "147") (name "unconnected-(TEENSY++-45,A7-PadF7)") (class "Default")
      (node (ref "TEENSY++") (pin "F7") (pinfunction "45,A7_F7") (pintype "bidirectional"))
    )
    (net (code "148") (name "unconnected-(TEENSY++-AREF-PadREF)") (class "Default")
      (node (ref "TEENSY++") (pin "REF") (pinfunction "AREF_REF") (pintype "input"))
    )
    (net (code "149") (name "unconnected-(TEENSY++-Pad+5V)") (class "Default")
      (node (ref "TEENSY++") (pin "+5V") (pinfunction "+5V_+5V") (pintype "power_in"))
    )
    (net (code "150") (name "unconnected-(TEENSY++-_RST-PadRST)") (class "Default")
      (node (ref "TEENSY++") (pin "RST") (pinfunction "_RST_RST") (pintype "input"))
    )
  )
)
